# main.net
KiCad netlist of a schematic drawn in Altium Designer
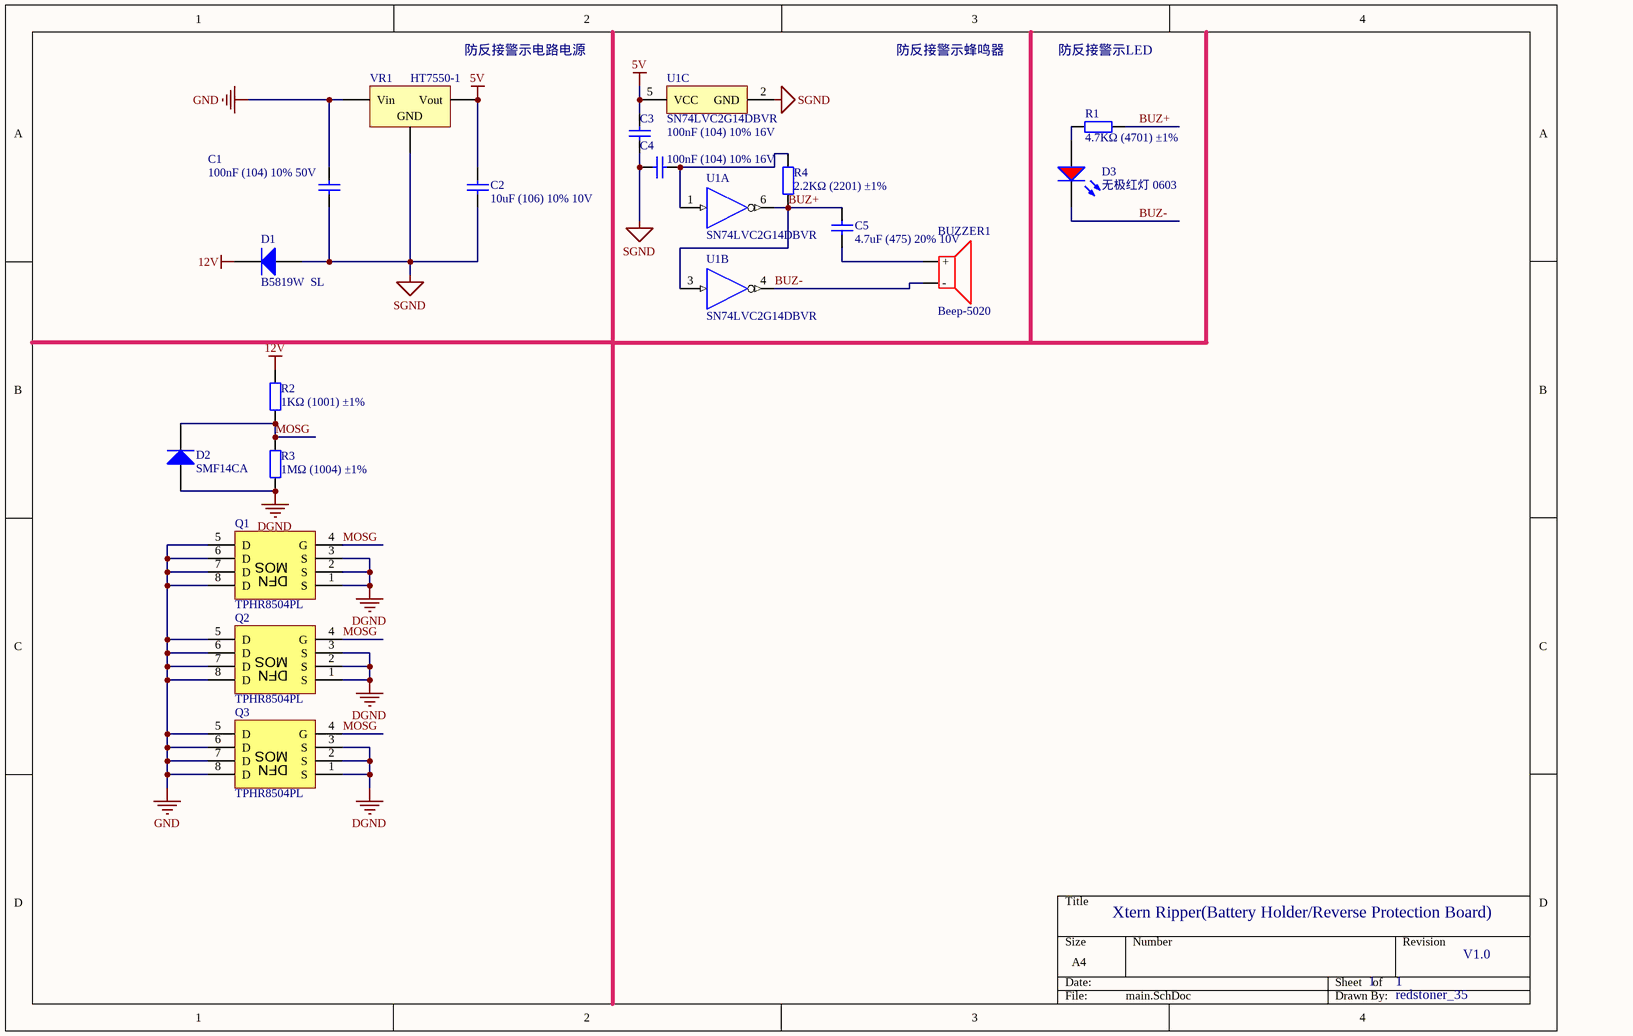
[diagram p0: main.SchDoc]

(export (version "E")
  (design (tool "Eeschema 10.0.6"))
  (components
    (comp (ref "BUZZER1")
      (value "Beep-5020")
      (footprint "5020BUZZER")
      (description "贴片蜂鸣器5020最小封装")
      (libsource (lib "我的元件") (part "Beep-5020"))
    )
    (comp (ref "C1")
      (value "100nF (104) 10% 50V")
      (footprint "0603_C")
      (description "贴片电容")
      (libsource (lib "Miscellaneous Devices LC") (part "0603 100nF (104) 10% 50V"))
    )
    (comp (ref "C2")
      (value "10uF (106) 10% 10V")
      (footprint "0603_C")
      (description "贴片电容")
      (libsource (lib "Miscellaneous Devices LC") (part "0603 10uF (106) 10% 10V"))
    )
    (comp (ref "C3")
      (value "100nF (104) 10% 16V")
      (footprint "0402_C")
      (description "贴片电容")
      (libsource (lib "Miscellaneous Devices LC") (part "0402 100nF (104) 10% 16V"))
    )
    (comp (ref "C4")
      (value "100nF (104) 10% 16V")
      (footprint "0402_C")
      (description "贴片电容")
      (libsource (lib "Miscellaneous Devices LC") (part "0402 100nF (104) 10% 16V"))
    )
    (comp (ref "C5")
      (value "4.7uF (475) 20% 10V")
      (footprint "0402_C")
      (description "贴片电容")
      (libsource (lib "Miscellaneous Devices LC") (part "0402 4.7uF (475) 20% 10V"))
    )
    (comp (ref "D1")
      (value "B5819W  SL")
      (footprint "SOD-123")
      (description "肖特基二极管")
      (libsource (lib "Miscellaneous Devices LC") (part "SOD-123 B5819W  SL"))
    )
    (comp (ref "D2")
      (value "SMF14CA")
      (footprint "SOD-123")
      (description "TVS二极管")
      (libsource (lib "Miscellaneous Devices LC") (part "SOD-123 B5819W  SL"))
    )
    (comp (ref "D3")
      (value "无极红灯 0603")
      (footprint "0603_LED_S1")
      (description "发光二极管")
      (libsource (lib "Miscellaneous Devices LC") (part "0603 红灯"))
    )
    (comp (ref "Q1")
      (value "TPHR8504PL")
      (footprint "SON/DFN5x6(MOS)")
      (description "N channel MOSFET 0.7mR 150A 40V")
      (libsource (lib "custom") (part "SON/DFN5x6 MOS"))
    )
    (comp (ref "Q2")
      (value "TPHR8504PL")
      (footprint "SON/DFN5x6(MOS)")
      (description "N channel MOSFET 0.7mR 150A 40V")
      (libsource (lib "custom") (part "SON/DFN5x6 MOS"))
    )
    (comp (ref "Q3")
      (value "TPHR8504PL")
      (footprint "SON/DFN5x6(MOS)")
      (description "N channel MOSFET 0.7mR 150A 40V")
      (libsource (lib "custom") (part "SON/DFN5x6 MOS"))
    )
    (comp (ref "R1")
      (value "4.7KΩ (4701) ±1%")
      (footprint "0402_R")
      (description "贴片电阻")
      (libsource (lib "Miscellaneous Devices LC") (part "0402 4.7KΩ (4701) 1%"))
    )
    (comp (ref "R2")
      (value "1KΩ (1001) ±1%")
      (footprint "0805_R")
      (description "贴片电阻")
      (libsource (lib "Miscellaneous Devices LC") (part "0805 1KΩ (1001) 1%"))
    )
    (comp (ref "R3")
      (value "1MΩ (1004) ±1%")
      (footprint "0402_R")
      (description "贴片电阻")
      (libsource (lib "Miscellaneous Devices LC") (part "0402 1MΩ (1004) 1%"))
    )
    (comp (ref "R4")
      (value "2.2KΩ (2201) ±1%")
      (footprint "0402_R")
      (description "贴片电阻")
      (libsource (lib "Miscellaneous Devices LC") (part "0402 2.2KΩ (2201) 1%"))
    )
    (comp (ref "U1")
      (value "SN74LVC2G14DBVR")
      (footprint "DBV0006A_N")
      (description "Dual Schmitt-Trigger Inverter, DBV0006A, LARGE T&R")
      (fields
        (field (name "GENERIC PART NUMBER") "SN74LVC2G14")
        (field (name "MANUFACTURER") "Texas Instruments")
      )
      (libsource (lib "TI_Logic_Little_Logic") (part "SN74LVC2G14DBVR"))
    )
    (comp (ref "VR1")
      (value "HT7550-1")
      (footprint "SOT-89(SOT-89-3)")
      (description "低压差线性稳压(LDO)")
      (libsource (lib "Miscellaneous Devices LC") (part "SOT-89 HT7550-1"))
    )
  )
  (nets
    (net (code "1") (name "/BUZ+") (class "Default")
      (node (ref "C5") (pin "2") (pinfunction "2_2") (pintype "passive"))
      (node (ref "R1") (pin "2") (pinfunction "2_2") (pintype "passive"))
      (node (ref "R4") (pin "1") (pinfunction "1_1") (pintype "passive"))
      (node (ref "U1") (pin "3") (pinfunction "2A_3") (pintype "input"))
      (node (ref "U1") (pin "6") (pinfunction "1Y_6") (pintype "output"))
    )
    (net (code "2") (name "/BUZ-") (class "Default")
      (node (ref "BUZZER1") (pin "2") (pinfunction "-_2") (pintype "passive"))
      (node (ref "D3") (pin "K") (pinfunction "K_K") (pintype "passive"))
      (node (ref "U1") (pin "4") (pinfunction "2Y_4") (pintype "output"))
    )
    (net (code "3") (name "/MOSG") (class "Default")
      (node (ref "D2") (pin "2") (pinfunction "K_2") (pintype "passive"))
      (node (ref "Q1") (pin "4") (pinfunction "G_4") (pintype "passive"))
      (node (ref "Q2") (pin "4") (pinfunction "G_4") (pintype "passive"))
      (node (ref "Q3") (pin "4") (pinfunction "G_4") (pintype "passive"))
      (node (ref "R2") (pin "1") (pinfunction "1_1") (pintype "passive"))
      (node (ref "R3") (pin "2") (pinfunction "2_2") (pintype "passive"))
    )
    (net (code "4") (name "5V") (class "Default")
      (node (ref "C2") (pin "2") (pinfunction "2_2") (pintype "passive"))
      (node (ref "C3") (pin "2") (pinfunction "2_2") (pintype "passive"))
      (node (ref "U1") (pin "5") (pinfunction "VCC_5") (pintype "power_in"))
      (node (ref "VR1") (pin "3") (pinfunction "Vout_3") (pintype "passive"))
    )
    (net (code "5") (name "12V") (class "Default")
      (node (ref "D1") (pin "2") (pinfunction "K_2") (pintype "passive"))
      (node (ref "R2") (pin "2") (pinfunction "2_2") (pintype "passive"))
    )
    (net (code "6") (name "DGND") (class "Default")
      (node (ref "D2") (pin "1") (pinfunction "A_1") (pintype "passive"))
      (node (ref "Q1") (pin "1") (pinfunction "S_1") (pintype "passive"))
      (node (ref "Q1") (pin "2") (pinfunction "S_2") (pintype "passive"))
      (node (ref "Q1") (pin "3") (pinfunction "S_3") (pintype "passive"))
      (node (ref "Q2") (pin "1") (pinfunction "S_1") (pintype "passive"))
      (node (ref "Q2") (pin "2") (pinfunction "S_2") (pintype "passive"))
      (node (ref "Q2") (pin "3") (pinfunction "S_3") (pintype "passive"))
      (node (ref "Q3") (pin "1") (pinfunction "S_1") (pintype "passive"))
      (node (ref "Q3") (pin "2") (pinfunction "S_2") (pintype "passive"))
      (node (ref "Q3") (pin "3") (pinfunction "S_3") (pintype "passive"))
      (node (ref "R3") (pin "1") (pinfunction "1_1") (pintype "passive"))
    )
    (net (code "7") (name "GND") (class "Default")
      (node (ref "C1") (pin "2") (pinfunction "2_2") (pintype "passive"))
      (node (ref "Q1") (pin "5") (pinfunction "D_5") (pintype "passive"))
      (node (ref "Q1") (pin "6") (pinfunction "D_6") (pintype "passive"))
      (node (ref "Q1") (pin "7") (pinfunction "D_7") (pintype "passive"))
      (node (ref "Q1") (pin "8") (pinfunction "D_8") (pintype "passive"))
      (node (ref "Q2") (pin "5") (pinfunction "D_5") (pintype "passive"))
      (node (ref "Q2") (pin "6") (pinfunction "D_6") (pintype "passive"))
      (node (ref "Q2") (pin "7") (pinfunction "D_7") (pintype "passive"))
      (node (ref "Q2") (pin "8") (pinfunction "D_8") (pintype "passive"))
      (node (ref "Q3") (pin "5") (pinfunction "D_5") (pintype "passive"))
      (node (ref "Q3") (pin "6") (pinfunction "D_6") (pintype "passive"))
      (node (ref "Q3") (pin "7") (pinfunction "D_7") (pintype "passive"))
      (node (ref "Q3") (pin "8") (pinfunction "D_8") (pintype "passive"))
      (node (ref "VR1") (pin "2") (pinfunction "Vin_2") (pintype "passive"))
    )
    (net (code "8") (name "Net-(BUZZER1-+)") (class "Default")
      (node (ref "BUZZER1") (pin "1") (pinfunction "+_1") (pintype "passive"))
      (node (ref "C5") (pin "1") (pinfunction "1_1") (pintype "passive"))
    )
    (net (code "9") (name "Net-(D3-PadA)") (class "Default")
      (node (ref "D3") (pin "A") (pinfunction "A_A") (pintype "passive"))
      (node (ref "R1") (pin "1") (pinfunction "1_1") (pintype "passive"))
    )
    (net (code "10") (name "Net-(U1A-1A)") (class "Default")
      (node (ref "C4") (pin "1") (pinfunction "1_1") (pintype "passive"))
      (node (ref "R4") (pin "2") (pinfunction "2_2") (pintype "passive"))
      (node (ref "U1") (pin "1") (pinfunction "1A_1") (pintype "input"))
    )
    (net (code "11") (name "SGND") (class "Default")
      (node (ref "C1") (pin "1") (pinfunction "1_1") (pintype "passive"))
      (node (ref "C2") (pin "1") (pinfunction "1_1") (pintype "passive"))
      (node (ref "C3") (pin "1") (pinfunction "1_1") (pintype "passive"))
      (node (ref "C4") (pin "2") (pinfunction "2_2") (pintype "passive"))
      (node (ref "D1") (pin "1") (pinfunction "A_1") (pintype "passive"))
      (node (ref "U1") (pin "2") (pinfunction "GND_2") (pintype "power_in"))
      (node (ref "VR1") (pin "1") (pinfunction "GND_1") (pintype "passive"))
    )
  )
)
